# long.net
KiCad netlist of a schematic drawn in EAGLE
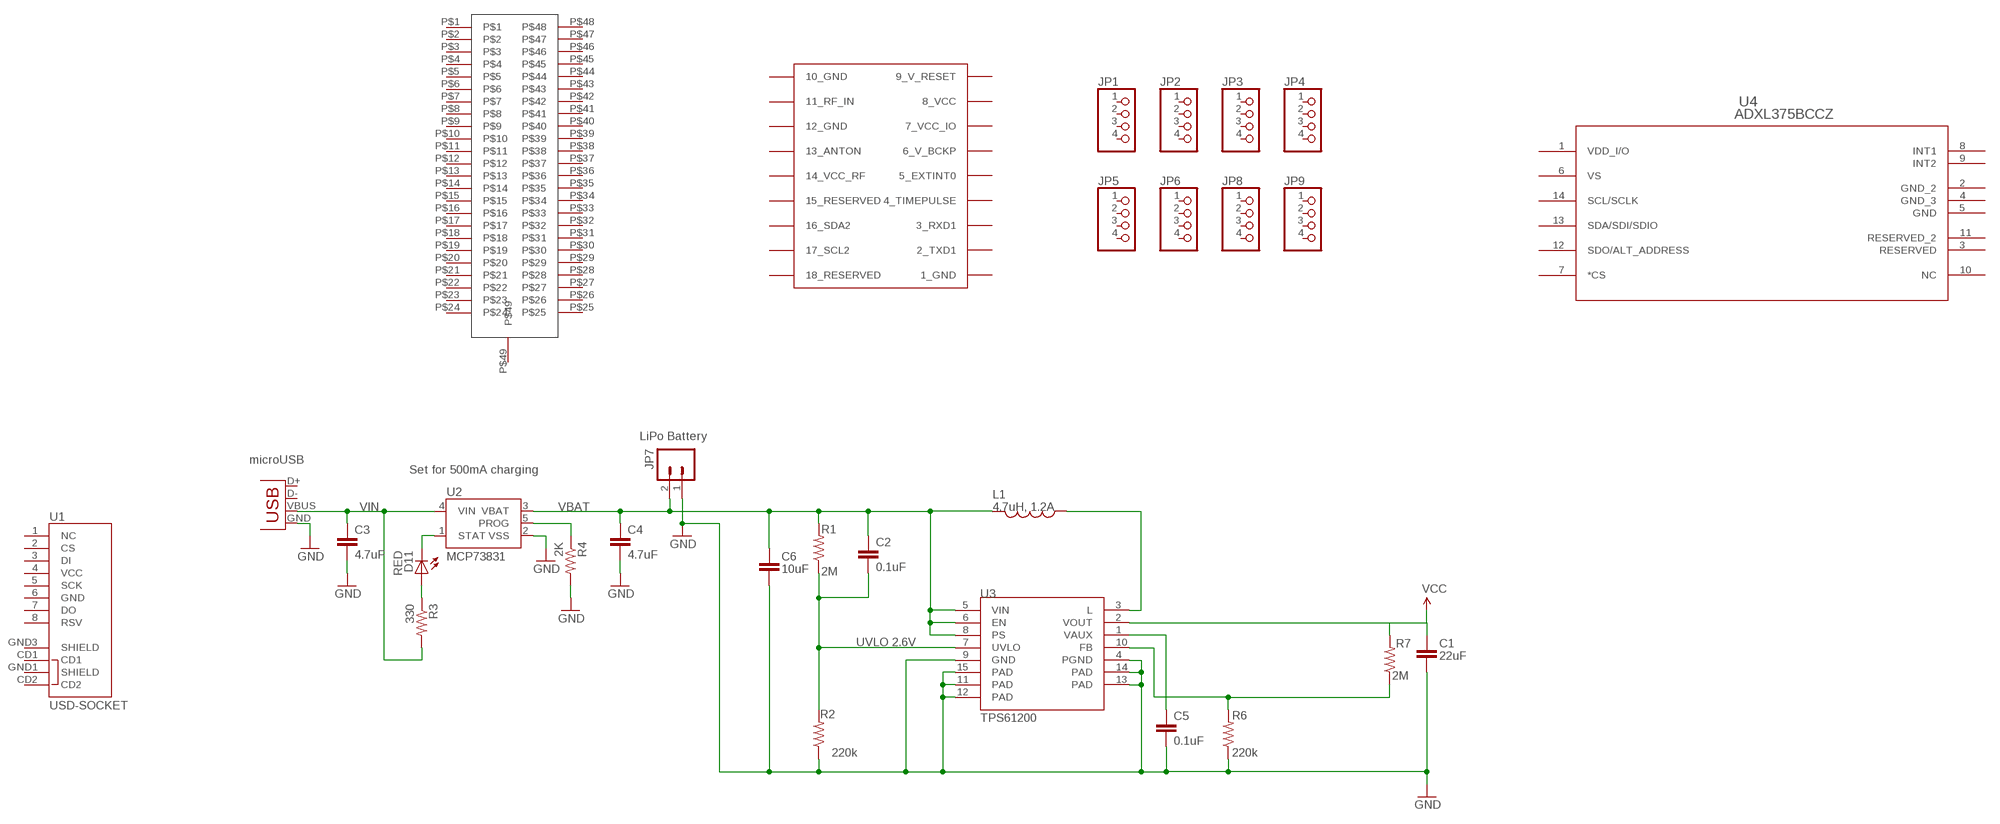
[diagram p0: schematic, sheet 1]

(export (version "E")
  (design (tool "Eeschema 10.0.6"))
  (components
    (comp (ref "C1")
      (value "22uF")
      (footprint "eagle-import:0805")
      (libsource (lib "eagle-import") (part "CAP0805"))
    )
    (comp (ref "C2")
      (value "0.1uF")
      (footprint "eagle-import:0603-CAP")
      (libsource (lib "eagle-import") (part "CAP0603-CAP"))
    )
    (comp (ref "C3")
      (value "4.7uF")
      (footprint "eagle-import:0402-CAP")
      (libsource (lib "eagle-import") (part "CAP0402-CAP"))
    )
    (comp (ref "C4")
      (value "4.7uF")
      (footprint "eagle-import:0402-CAP")
      (libsource (lib "eagle-import") (part "CAP0402-CAP"))
    )
    (comp (ref "C5")
      (value "0.1uF")
      (footprint "eagle-import:0603-CAP")
      (libsource (lib "eagle-import") (part "CAP0603-CAP"))
    )
    (comp (ref "C6")
      (value "10uF")
      (footprint "eagle-import:1206")
      (libsource (lib "eagle-import") (part "CAP1206"))
    )
    (comp (ref "D11")
      (value "RED")
      (footprint "eagle-import:LED-0603")
      (libsource (lib "eagle-import") (part "LED0603"))
    )
    (comp (ref "JP1")
      (value "PINHD-1X4")
      (footprint "eagle-import:1X04")
      (libsource (lib "eagle-import") (part "PINHD-1X4"))
    )
    (comp (ref "JP2")
      (value "PINHD-1X4")
      (footprint "eagle-import:1X04")
      (libsource (lib "eagle-import") (part "PINHD-1X4"))
    )
    (comp (ref "JP3")
      (value "PINHD-1X4")
      (footprint "eagle-import:1X04")
      (libsource (lib "eagle-import") (part "PINHD-1X4"))
    )
    (comp (ref "JP4")
      (value "PINHD-1X4")
      (footprint "eagle-import:1X04")
      (libsource (lib "eagle-import") (part "PINHD-1X4"))
    )
    (comp (ref "JP5")
      (value "PINHD-1X4")
      (footprint "eagle-import:1X04")
      (libsource (lib "eagle-import") (part "PINHD-1X4"))
    )
    (comp (ref "JP6")
      (value "PINHD-1X4")
      (footprint "eagle-import:1X04")
      (libsource (lib "eagle-import") (part "PINHD-1X4"))
    )
    (comp (ref "JP7")
      (value "LiPo Battery")
      (footprint "eagle-import:JST-2-SMD")
      (libsource (lib "eagle-import") (part "M02-JST-2MM-SMT"))
    )
    (comp (ref "JP8")
      (value "PINHD-1X4")
      (footprint "eagle-import:1X04")
      (libsource (lib "eagle-import") (part "PINHD-1X4"))
    )
    (comp (ref "JP9")
      (value "PINHD-1X4")
      (footprint "eagle-import:1X04")
      (libsource (lib "eagle-import") (part "PINHD-1X4"))
    )
    (comp (ref "L1")
      (value "4.7uH, 1.2A")
      (footprint "eagle-import:CDRH2D09")
      (libsource (lib "eagle-import") (part "INDUCTOR."))
    )
    (comp (ref "R1")
      (value "2M")
      (footprint "eagle-import:0603-RES")
      (libsource (lib "eagle-import") (part "RESISTOR0603-RES"))
    )
    (comp (ref "R2")
      (value "220k")
      (footprint "eagle-import:0603-RES")
      (libsource (lib "eagle-import") (part "RESISTOR0603-RES"))
    )
    (comp (ref "R3")
      (value "330")
      (footprint "eagle-import:0402-RES")
      (libsource (lib "eagle-import") (part "RESISTOR0402-RES"))
    )
    (comp (ref "R4")
      (value "2K")
      (footprint "eagle-import:0402-RES")
      (libsource (lib "eagle-import") (part "RESISTOR0402-RES"))
    )
    (comp (ref "R6")
      (value "220k")
      (footprint "eagle-import:0603-RES")
      (libsource (lib "eagle-import") (part "RESISTOR0603-RES"))
    )
    (comp (ref "R7")
      (value "2M")
      (footprint "eagle-import:0603-RES")
      (libsource (lib "eagle-import") (part "RESISTOR0603-RES"))
    )
    (comp (ref "U$1")
      (value "STM32F411CEU6")
      (footprint "eagle-import:STM32F411CEU6")
      (libsource (lib "eagle-import") (part "STM32F411CEU6"))
    )
    (comp (ref "U$2")
      (value "UBLOX_MAX")
      (footprint "eagle-import:UBLOX_MAX")
      (libsource (lib "eagle-import") (part "UBLOX_MAX"))
    )
    (comp (ref "U1")
      (value "USD-SOCKET")
      (footprint "eagle-import:MICROSD_1_1")
      (libsource (lib "eagle-import") (part "USD-SOCKET"))
    )
    (comp (ref "U2")
      (value "MCP73831")
      (footprint "eagle-import:SOT23-5")
      (libsource (lib "eagle-import") (part "MCP73831"))
    )
    (comp (ref "U3")
      (value "TPS61200")
      (footprint "eagle-import:QFN-10_PAD")
      (libsource (lib "eagle-import") (part "TPS61200"))
    )
    (comp (ref "U4")
      (value "ADXL375BCCZ")
      (footprint "eagle-import:LGA_CC-14-1")
      (libsource (lib "eagle-import") (part "ADXL375BCCZ"))
    )
    (comp (ref "X1")
      (value "Micro USB")
      (footprint "eagle-import:USB-MICROB")
      (libsource (lib "eagle-import") (part "USB-MICROB"))
    )
  )
  (nets
    (net (code "1") (name "/1_GND") (class "Default")
      (node (ref "U$2") (pin "1_GND") (pinfunction "1_GND_1_GND") (pintype "power_in"))
    )
    (net (code "2") (name "/7_VCC_IO") (class "Default")
      (node (ref "U$2") (pin "7_VCC_IO") (pinfunction "7_VCC_IO_7_VCC_IO") (pintype "power_in"))
    )
    (net (code "3") (name "/8_VCC") (class "Default")
      (node (ref "U$2") (pin "8_VCC") (pinfunction "8_VCC_8_VCC") (pintype "power_in"))
    )
    (net (code "4") (name "/9_V_RESET") (class "Default")
      (node (ref "U$2") (pin "9_V_RESET") (pinfunction "9_V_RESET_9_V_RESET") (pintype "power_in"))
    )
    (net (code "5") (name "/10_GND") (class "Default")
      (node (ref "U$2") (pin "10_GND") (pinfunction "10_GND_10_GND") (pintype "power_in"))
    )
    (net (code "6") (name "/12_GND") (class "Default")
      (node (ref "U$2") (pin "12_GND") (pinfunction "12_GND_12_GND") (pintype "power_in"))
    )
    (net (code "7") (name "/VBAT") (class "Default")
      (node (ref "C2") (pin "1") (pinfunction "1_1") (pintype "passive"))
      (node (ref "C4") (pin "1") (pinfunction "1_1") (pintype "passive"))
      (node (ref "C6") (pin "1") (pinfunction "1_1") (pintype "passive"))
      (node (ref "JP7") (pin "2") (pinfunction "2_2") (pintype "passive"))
      (node (ref "L1") (pin "P$2") (pinfunction "2_P$2") (pintype "passive"))
      (node (ref "R1") (pin "2") (pinfunction "2_2") (pintype "passive"))
      (node (ref "U2") (pin "3") (pinfunction "VBAT_3") (pintype "power_in"))
      (node (ref "U3") (pin "5") (pinfunction "VIN_5") (pintype "power_in"))
      (node (ref "U3") (pin "6") (pinfunction "EN_6") (pintype "input"))
      (node (ref "U3") (pin "8") (pinfunction "PS_8") (pintype "input"))
    )
    (net (code "8") (name "/VIN") (class "Default")
      (node (ref "C3") (pin "1") (pinfunction "1_1") (pintype "passive"))
      (node (ref "R3") (pin "2") (pinfunction "2_2") (pintype "passive"))
      (node (ref "U2") (pin "4") (pinfunction "VIN_4") (pintype "power_in"))
      (node (ref "X1") (pin "VBUS") (pinfunction "VBUS_VBUS") (pintype "bidirectional"))
    )
    (net (code "9") (name "GND") (class "Default")
      (node (ref "C1") (pin "2") (pinfunction "2_2") (pintype "passive"))
      (node (ref "C3") (pin "2") (pinfunction "2_2") (pintype "passive"))
      (node (ref "C4") (pin "2") (pinfunction "2_2") (pintype "passive"))
      (node (ref "C5") (pin "2") (pinfunction "2_2") (pintype "passive"))
      (node (ref "C6") (pin "2") (pinfunction "2_2") (pintype "passive"))
      (node (ref "JP7") (pin "1") (pinfunction "1_1") (pintype "passive"))
      (node (ref "R2") (pin "1") (pinfunction "1_1") (pintype "passive"))
      (node (ref "R4") (pin "2") (pinfunction "2_2") (pintype "passive"))
      (node (ref "R6") (pin "1") (pinfunction "1_1") (pintype "passive"))
      (node (ref "U2") (pin "2") (pinfunction "VSS_2") (pintype "power_in"))
      (node (ref "U3") (pin "11") (pinfunction "PAD_11") (pintype "power_in"))
      (node (ref "U3") (pin "12") (pinfunction "PAD_12") (pintype "power_in"))
      (node (ref "U3") (pin "13") (pinfunction "PAD_13") (pintype "power_in"))
      (node (ref "U3") (pin "14") (pinfunction "PAD_14") (pintype "power_in"))
      (node (ref "U3") (pin "15") (pinfunction "PAD_15") (pintype "power_in"))
      (node (ref "U3") (pin "4") (pinfunction "PGND_4") (pintype "power_in"))
      (node (ref "U3") (pin "9") (pinfunction "GND_9") (pintype "power_in"))
      (node (ref "X1") (pin "GND") (pinfunction "GND_GND") (pintype "bidirectional"))
    )
    (net (code "10") (name "Net-(D11-PadA)") (class "Default")
      (node (ref "D11") (pin "A") (pinfunction "A_A") (pintype "passive"))
      (node (ref "R3") (pin "1") (pinfunction "1_1") (pintype "passive"))
    )
    (net (code "11") (name "Net-(L1-1)") (class "Default")
      (node (ref "L1") (pin "P$1") (pinfunction "1_P$1") (pintype "passive"))
      (node (ref "U3") (pin "3") (pinfunction "L_3") (pintype "passive"))
    )
    (net (code "12") (name "Net-(U2-PROG)") (class "Default")
      (node (ref "R4") (pin "1") (pinfunction "1_1") (pintype "passive"))
      (node (ref "U2") (pin "5") (pinfunction "PROG_5") (pintype "input"))
    )
    (net (code "13") (name "Net-(U2-STAT)") (class "Default")
      (node (ref "D11") (pin "C") (pinfunction "C_C") (pintype "passive"))
      (node (ref "U2") (pin "1") (pinfunction "STAT_1") (pintype "output"))
    )
    (net (code "14") (name "Net-(U3-FB)") (class "Default")
      (node (ref "R6") (pin "2") (pinfunction "2_2") (pintype "passive"))
      (node (ref "R7") (pin "1") (pinfunction "1_1") (pintype "passive"))
      (node (ref "U3") (pin "10") (pinfunction "FB_10") (pintype "passive"))
    )
    (net (code "15") (name "Net-(U3-UVLO)") (class "Default")
      (node (ref "C2") (pin "2") (pinfunction "2_2") (pintype "passive"))
      (node (ref "R1") (pin "1") (pinfunction "1_1") (pintype "passive"))
      (node (ref "R2") (pin "2") (pinfunction "2_2") (pintype "passive"))
      (node (ref "U3") (pin "7") (pinfunction "UVLO_7") (pintype "passive"))
    )
    (net (code "16") (name "Net-(U3-VAUX)") (class "Default")
      (node (ref "C5") (pin "1") (pinfunction "1_1") (pintype "passive"))
      (node (ref "U3") (pin "1") (pinfunction "VAUX_1") (pintype "passive"))
    )
    (net (code "17") (name "VCC") (class "Default")
      (node (ref "C1") (pin "1") (pinfunction "1_1") (pintype "passive"))
      (node (ref "R7") (pin "2") (pinfunction "2_2") (pintype "passive"))
      (node (ref "U3") (pin "2") (pinfunction "VOUT_2") (pintype "passive"))
    )
    (net (code "18") (name "unconnected-(JP1-Pad1)") (class "Default")
      (node (ref "JP1") (pin "1") (pinfunction "1_1") (pintype "passive"))
    )
    (net (code "19") (name "unconnected-(JP1-Pad2)") (class "Default")
      (node (ref "JP1") (pin "2") (pinfunction "2_2") (pintype "passive"))
    )
    (net (code "20") (name "unconnected-(JP1-Pad3)") (class "Default")
      (node (ref "JP1") (pin "3") (pinfunction "3_3") (pintype "passive"))
    )
    (net (code "21") (name "unconnected-(JP1-Pad4)") (class "Default")
      (node (ref "JP1") (pin "4") (pinfunction "4_4") (pintype "passive"))
    )
    (net (code "22") (name "unconnected-(JP2-Pad1)") (class "Default")
      (node (ref "JP2") (pin "1") (pinfunction "1_1") (pintype "passive"))
    )
    (net (code "23") (name "unconnected-(JP2-Pad2)") (class "Default")
      (node (ref "JP2") (pin "2") (pinfunction "2_2") (pintype "passive"))
    )
    (net (code "24") (name "unconnected-(JP2-Pad3)") (class "Default")
      (node (ref "JP2") (pin "3") (pinfunction "3_3") (pintype "passive"))
    )
    (net (code "25") (name "unconnected-(JP2-Pad4)") (class "Default")
      (node (ref "JP2") (pin "4") (pinfunction "4_4") (pintype "passive"))
    )
    (net (code "26") (name "unconnected-(JP3-Pad1)") (class "Default")
      (node (ref "JP3") (pin "1") (pinfunction "1_1") (pintype "passive"))
    )
    (net (code "27") (name "unconnected-(JP3-Pad2)") (class "Default")
      (node (ref "JP3") (pin "2") (pinfunction "2_2") (pintype "passive"))
    )
    (net (code "28") (name "unconnected-(JP3-Pad3)") (class "Default")
      (node (ref "JP3") (pin "3") (pinfunction "3_3") (pintype "passive"))
    )
    (net (code "29") (name "unconnected-(JP3-Pad4)") (class "Default")
      (node (ref "JP3") (pin "4") (pinfunction "4_4") (pintype "passive"))
    )
    (net (code "30") (name "unconnected-(JP4-Pad1)") (class "Default")
      (node (ref "JP4") (pin "1") (pinfunction "1_1") (pintype "passive"))
    )
    (net (code "31") (name "unconnected-(JP4-Pad2)") (class "Default")
      (node (ref "JP4") (pin "2") (pinfunction "2_2") (pintype "passive"))
    )
    (net (code "32") (name "unconnected-(JP4-Pad3)") (class "Default")
      (node (ref "JP4") (pin "3") (pinfunction "3_3") (pintype "passive"))
    )
    (net (code "33") (name "unconnected-(JP4-Pad4)") (class "Default")
      (node (ref "JP4") (pin "4") (pinfunction "4_4") (pintype "passive"))
    )
    (net (code "34") (name "unconnected-(JP5-Pad1)") (class "Default")
      (node (ref "JP5") (pin "1") (pinfunction "1_1") (pintype "passive"))
    )
    (net (code "35") (name "unconnected-(JP5-Pad2)") (class "Default")
      (node (ref "JP5") (pin "2") (pinfunction "2_2") (pintype "passive"))
    )
    (net (code "36") (name "unconnected-(JP5-Pad3)") (class "Default")
      (node (ref "JP5") (pin "3") (pinfunction "3_3") (pintype "passive"))
    )
    (net (code "37") (name "unconnected-(JP5-Pad4)") (class "Default")
      (node (ref "JP5") (pin "4") (pinfunction "4_4") (pintype "passive"))
    )
    (net (code "38") (name "unconnected-(JP6-Pad1)") (class "Default")
      (node (ref "JP6") (pin "1") (pinfunction "1_1") (pintype "passive"))
    )
    (net (code "39") (name "unconnected-(JP6-Pad2)") (class "Default")
      (node (ref "JP6") (pin "2") (pinfunction "2_2") (pintype "passive"))
    )
    (net (code "40") (name "unconnected-(JP6-Pad3)") (class "Default")
      (node (ref "JP6") (pin "3") (pinfunction "3_3") (pintype "passive"))
    )
    (net (code "41") (name "unconnected-(JP6-Pad4)") (class "Default")
      (node (ref "JP6") (pin "4") (pinfunction "4_4") (pintype "passive"))
    )
    (net (code "42") (name "unconnected-(JP8-Pad1)") (class "Default")
      (node (ref "JP8") (pin "1") (pinfunction "1_1") (pintype "passive"))
    )
    (net (code "43") (name "unconnected-(JP8-Pad2)") (class "Default")
      (node (ref "JP8") (pin "2") (pinfunction "2_2") (pintype "passive"))
    )
    (net (code "44") (name "unconnected-(JP8-Pad3)") (class "Default")
      (node (ref "JP8") (pin "3") (pinfunction "3_3") (pintype "passive"))
    )
    (net (code "45") (name "unconnected-(JP8-Pad4)") (class "Default")
      (node (ref "JP8") (pin "4") (pinfunction "4_4") (pintype "passive"))
    )
    (net (code "46") (name "unconnected-(JP9-Pad1)") (class "Default")
      (node (ref "JP9") (pin "1") (pinfunction "1_1") (pintype "passive"))
    )
    (net (code "47") (name "unconnected-(JP9-Pad2)") (class "Default")
      (node (ref "JP9") (pin "2") (pinfunction "2_2") (pintype "passive"))
    )
    (net (code "48") (name "unconnected-(JP9-Pad3)") (class "Default")
      (node (ref "JP9") (pin "3") (pinfunction "3_3") (pintype "passive"))
    )
    (net (code "49") (name "unconnected-(JP9-Pad4)") (class "Default")
      (node (ref "JP9") (pin "4") (pinfunction "4_4") (pintype "passive"))
    )
    (net (code "50") (name "unconnected-(U$1-PadP$1)") (class "Default")
      (node (ref "U$1") (pin "P$1") (pinfunction "P$1_P$1") (pintype "bidirectional"))
    )
    (net (code "51") (name "unconnected-(U$1-PadP$2)") (class "Default")
      (node (ref "U$1") (pin "P$2") (pinfunction "P$2_P$2") (pintype "bidirectional"))
    )
    (net (code "52") (name "unconnected-(U$1-PadP$3)") (class "Default")
      (node (ref "U$1") (pin "P$3") (pinfunction "P$3_P$3") (pintype "bidirectional"))
    )
    (net (code "53") (name "unconnected-(U$1-PadP$4)") (class "Default")
      (node (ref "U$1") (pin "P$4") (pinfunction "P$4_P$4") (pintype "bidirectional"))
    )
    (net (code "54") (name "unconnected-(U$1-PadP$5)") (class "Default")
      (node (ref "U$1") (pin "P$5") (pinfunction "P$5_P$5") (pintype "bidirectional"))
    )
    (net (code "55") (name "unconnected-(U$1-PadP$6)") (class "Default")
      (node (ref "U$1") (pin "P$6") (pinfunction "P$6_P$6") (pintype "bidirectional"))
    )
    (net (code "56") (name "unconnected-(U$1-PadP$7)") (class "Default")
      (node (ref "U$1") (pin "P$7") (pinfunction "P$7_P$7") (pintype "bidirectional"))
    )
    (net (code "57") (name "unconnected-(U$1-PadP$8)") (class "Default")
      (node (ref "U$1") (pin "P$8") (pinfunction "P$8_P$8") (pintype "bidirectional"))
    )
    (net (code "58") (name "unconnected-(U$1-PadP$9)") (class "Default")
      (node (ref "U$1") (pin "P$9") (pinfunction "P$9_P$9") (pintype "bidirectional"))
    )
    (net (code "59") (name "unconnected-(U$1-PadP$10)") (class "Default")
      (node (ref "U$1") (pin "P$10") (pinfunction "P$10_P$10") (pintype "bidirectional"))
    )
    (net (code "60") (name "unconnected-(U$1-PadP$11)") (class "Default")
      (node (ref "U$1") (pin "P$11") (pinfunction "P$11_P$11") (pintype "bidirectional"))
    )
    (net (code "61") (name "unconnected-(U$1-PadP$12)") (class "Default")
      (node (ref "U$1") (pin "P$12") (pinfunction "P$12_P$12") (pintype "bidirectional"))
    )
    (net (code "62") (name "unconnected-(U$1-PadP$13)") (class "Default")
      (node (ref "U$1") (pin "P$13") (pinfunction "P$13_P$13") (pintype "bidirectional"))
    )
    (net (code "63") (name "unconnected-(U$1-PadP$14)") (class "Default")
      (node (ref "U$1") (pin "P$14") (pinfunction "P$14_P$14") (pintype "bidirectional"))
    )
    (net (code "64") (name "unconnected-(U$1-PadP$15)") (class "Default")
      (node (ref "U$1") (pin "P$15") (pinfunction "P$15_P$15") (pintype "bidirectional"))
    )
    (net (code "65") (name "unconnected-(U$1-PadP$16)") (class "Default")
      (node (ref "U$1") (pin "P$16") (pinfunction "P$16_P$16") (pintype "bidirectional"))
    )
    (net (code "66") (name "unconnected-(U$1-PadP$17)") (class "Default")
      (node (ref "U$1") (pin "P$17") (pinfunction "P$17_P$17") (pintype "bidirectional"))
    )
    (net (code "67") (name "unconnected-(U$1-PadP$18)") (class "Default")
      (node (ref "U$1") (pin "P$18") (pinfunction "P$18_P$18") (pintype "bidirectional"))
    )
    (net (code "68") (name "unconnected-(U$1-PadP$19)") (class "Default")
      (node (ref "U$1") (pin "P$19") (pinfunction "P$19_P$19") (pintype "bidirectional"))
    )
    (net (code "69") (name "unconnected-(U$1-PadP$20)") (class "Default")
      (node (ref "U$1") (pin "P$20") (pinfunction "P$20_P$20") (pintype "bidirectional"))
    )
    (net (code "70") (name "unconnected-(U$1-PadP$21)") (class "Default")
      (node (ref "U$1") (pin "P$21") (pinfunction "P$21_P$21") (pintype "bidirectional"))
    )
    (net (code "71") (name "unconnected-(U$1-PadP$22)") (class "Default")
      (node (ref "U$1") (pin "P$22") (pinfunction "P$22_P$22") (pintype "bidirectional"))
    )
    (net (code "72") (name "unconnected-(U$1-PadP$23)") (class "Default")
      (node (ref "U$1") (pin "P$23") (pinfunction "P$23_P$23") (pintype "bidirectional"))
    )
    (net (code "73") (name "unconnected-(U$1-PadP$24)") (class "Default")
      (node (ref "U$1") (pin "P$24") (pinfunction "P$24_P$24") (pintype "bidirectional"))
    )
    (net (code "74") (name "unconnected-(U$1-PadP$25)") (class "Default")
      (node (ref "U$1") (pin "P$25") (pinfunction "P$25_P$25") (pintype "bidirectional"))
    )
    (net (code "75") (name "unconnected-(U$1-PadP$26)") (class "Default")
      (node (ref "U$1") (pin "P$26") (pinfunction "P$26_P$26") (pintype "bidirectional"))
    )
    (net (code "76") (name "unconnected-(U$1-PadP$27)") (class "Default")
      (node (ref "U$1") (pin "P$27") (pinfunction "P$27_P$27") (pintype "bidirectional"))
    )
    (net (code "77") (name "unconnected-(U$1-PadP$28)") (class "Default")
      (node (ref "U$1") (pin "P$28") (pinfunction "P$28_P$28") (pintype "bidirectional"))
    )
    (net (code "78") (name "unconnected-(U$1-PadP$29)") (class "Default")
      (node (ref "U$1") (pin "P$29") (pinfunction "P$29_P$29") (pintype "bidirectional"))
    )
    (net (code "79") (name "unconnected-(U$1-PadP$30)") (class "Default")
      (node (ref "U$1") (pin "P$30") (pinfunction "P$30_P$30") (pintype "bidirectional"))
    )
    (net (code "80") (name "unconnected-(U$1-PadP$31)") (class "Default")
      (node (ref "U$1") (pin "P$31") (pinfunction "P$31_P$31") (pintype "bidirectional"))
    )
    (net (code "81") (name "unconnected-(U$1-PadP$32)") (class "Default")
      (node (ref "U$1") (pin "P$32") (pinfunction "P$32_P$32") (pintype "bidirectional"))
    )
    (net (code "82") (name "unconnected-(U$1-PadP$33)") (class "Default")
      (node (ref "U$1") (pin "P$33") (pinfunction "P$33_P$33") (pintype "bidirectional"))
    )
    (net (code "83") (name "unconnected-(U$1-PadP$34)") (class "Default")
      (node (ref "U$1") (pin "P$34") (pinfunction "P$34_P$34") (pintype "bidirectional"))
    )
    (net (code "84") (name "unconnected-(U$1-PadP$35)") (class "Default")
      (node (ref "U$1") (pin "P$35") (pinfunction "P$35_P$35") (pintype "bidirectional"))
    )
    (net (code "85") (name "unconnected-(U$1-PadP$36)") (class "Default")
      (node (ref "U$1") (pin "P$36") (pinfunction "P$36_P$36") (pintype "bidirectional"))
    )
    (net (code "86") (name "unconnected-(U$1-PadP$37)") (class "Default")
      (node (ref "U$1") (pin "P$37") (pinfunction "P$37_P$37") (pintype "bidirectional"))
    )
    (net (code "87") (name "unconnected-(U$1-PadP$38)") (class "Default")
      (node (ref "U$1") (pin "P$38") (pinfunction "P$38_P$38") (pintype "bidirectional"))
    )
    (net (code "88") (name "unconnected-(U$1-PadP$39)") (class "Default")
      (node (ref "U$1") (pin "P$39") (pinfunction "P$39_P$39") (pintype "bidirectional"))
    )
    (net (code "89") (name "unconnected-(U$1-PadP$40)") (class "Default")
      (node (ref "U$1") (pin "P$40") (pinfunction "P$40_P$40") (pintype "bidirectional"))
    )
    (net (code "90") (name "unconnected-(U$1-PadP$41)") (class "Default")
      (node (ref "U$1") (pin "P$41") (pinfunction "P$41_P$41") (pintype "bidirectional"))
    )
    (net (code "91") (name "unconnected-(U$1-PadP$42)") (class "Default")
      (node (ref "U$1") (pin "P$42") (pinfunction "P$42_P$42") (pintype "bidirectional"))
    )
    (net (code "92") (name "unconnected-(U$1-PadP$43)") (class "Default")
      (node (ref "U$1") (pin "P$43") (pinfunction "P$43_P$43") (pintype "bidirectional"))
    )
    (net (code "93") (name "unconnected-(U$1-PadP$44)") (class "Default")
      (node (ref "U$1") (pin "P$44") (pinfunction "P$44_P$44") (pintype "bidirectional"))
    )
    (net (code "94") (name "unconnected-(U$1-PadP$45)") (class "Default")
      (node (ref "U$1") (pin "P$45") (pinfunction "P$45_P$45") (pintype "bidirectional"))
    )
    (net (code "95") (name "unconnected-(U$1-PadP$46)") (class "Default")
      (node (ref "U$1") (pin "P$46") (pinfunction "P$46_P$46") (pintype "bidirectional"))
    )
    (net (code "96") (name "unconnected-(U$1-PadP$47)") (class "Default")
      (node (ref "U$1") (pin "P$47") (pinfunction "P$47_P$47") (pintype "bidirectional"))
    )
    (net (code "97") (name "unconnected-(U$1-PadP$48)") (class "Default")
      (node (ref "U$1") (pin "P$48") (pinfunction "P$48_P$48") (pintype "bidirectional"))
    )
    (net (code "98") (name "unconnected-(U$1-PadP$49)") (class "Default")
      (node (ref "U$1") (pin "P$49") (pinfunction "P$49_P$49") (pintype "bidirectional"))
    )
    (net (code "99") (name "unconnected-(U$2-Pad2_TXD1)") (class "Default")
      (node (ref "U$2") (pin "2_TXD1") (pinfunction "2_TXD1_2_TXD1") (pintype "bidirectional"))
    )
    (net (code "100") (name "unconnected-(U$2-Pad3_RXD1)") (class "Default")
      (node (ref "U$2") (pin "3_RXD1") (pinfunction "3_RXD1_3_RXD1") (pintype "bidirectional"))
    )
    (net (code "101") (name "unconnected-(U$2-Pad4_TIMEPULSE)") (class "Default")
      (node (ref "U$2") (pin "4_TIMEPULSE") (pinfunction "4_TIMEPULSE_4_TIMEPULSE") (pintype "bidirectional"))
    )
    (net (code "102") (name "unconnected-(U$2-Pad5_EXTINT0)") (class "Default")
      (node (ref "U$2") (pin "5_EXTINT0") (pinfunction "5_EXTINT0_5_EXTINT0") (pintype "bidirectional"))
    )
    (net (code "103") (name "unconnected-(U$2-Pad6_V_BCKP)") (class "Default")
      (node (ref "U$2") (pin "6_V_BCKP") (pinfunction "6_V_BCKP_6_V_BCKP") (pintype "bidirectional"))
    )
    (net (code "104") (name "unconnected-(U$2-Pad11_RF_IN)") (class "Default")
      (node (ref "U$2") (pin "11_RF_IN") (pinfunction "11_RF_IN_11_RF_IN") (pintype "bidirectional"))
    )
    (net (code "105") (name "unconnected-(U$2-Pad13_ANTON)") (class "Default")
      (node (ref "U$2") (pin "13_ANTON") (pinfunction "13_ANTON_13_ANTON") (pintype "bidirectional"))
    )
    (net (code "106") (name "unconnected-(U$2-Pad14_VCC_RF)") (class "Default")
      (node (ref "U$2") (pin "14_VCC_RF") (pinfunction "14_VCC_RF_14_VCC_RF") (pintype "bidirectional"))
    )
    (net (code "107") (name "unconnected-(U$2-Pad15_RESERVED)") (class "Default")
      (node (ref "U$2") (pin "15_RESERVED") (pinfunction "15_RESERVED_15_RESERVED") (pintype "bidirectional"))
    )
    (net (code "108") (name "unconnected-(U$2-Pad16_SDA2)") (class "Default")
      (node (ref "U$2") (pin "16_SDA2") (pinfunction "16_SDA2_16_SDA2") (pintype "bidirectional"))
    )
    (net (code "109") (name "unconnected-(U$2-Pad17_SCL2)") (class "Default")
      (node (ref "U$2") (pin "17_SCL2") (pinfunction "17_SCL2_17_SCL2") (pintype "bidirectional"))
    )
    (net (code "110") (name "unconnected-(U$2-Pad18_RESERVED)") (class "Default")
      (node (ref "U$2") (pin "18_RESERVED") (pinfunction "18_RESERVED_18_RESERVED") (pintype "bidirectional"))
    )
    (net (code "111") (name "unconnected-(U1-CS-Pad2)") (class "Default")
      (node (ref "U1") (pin "2") (pinfunction "CS_2") (pintype "bidirectional"))
    )
    (net (code "112") (name "unconnected-(U1-DI-Pad3)") (class "Default")
      (node (ref "U1") (pin "3") (pinfunction "DI_3") (pintype "bidirectional"))
    )
    (net (code "113") (name "unconnected-(U1-DO-Pad7)") (class "Default")
      (node (ref "U1") (pin "7") (pinfunction "DO_7") (pintype "bidirectional"))
    )
    (net (code "114") (name "unconnected-(U1-GND-Pad6)") (class "Default")
      (node (ref "U1") (pin "6") (pinfunction "GND_6") (pintype "bidirectional"))
    )
    (net (code "115") (name "unconnected-(U1-NC-Pad1)") (class "Default")
      (node (ref "U1") (pin "1") (pinfunction "NC_1") (pintype "bidirectional"))
    )
    (net (code "116") (name "unconnected-(U1-PadCD1)") (class "Default")
      (node (ref "U1") (pin "CD1") (pinfunction "CD1_CD1") (pintype "bidirectional"))
    )
    (net (code "117") (name "unconnected-(U1-PadCD2)") (class "Default")
      (node (ref "U1") (pin "CD2") (pinfunction "CD2_CD2") (pintype "bidirectional"))
    )
    (net (code "118") (name "unconnected-(U1-RSV-Pad8)") (class "Default")
      (node (ref "U1") (pin "8") (pinfunction "RSV_8") (pintype "bidirectional"))
    )
    (net (code "119") (name "unconnected-(U1-SCK-Pad5)") (class "Default")
      (node (ref "U1") (pin "5") (pinfunction "SCK_5") (pintype "bidirectional"))
    )
    (net (code "120") (name "unconnected-(U1-SHIELD-PadGND1)") (class "Default")
      (node (ref "U1") (pin "GND1") (pinfunction "SHIELD_GND1") (pintype "bidirectional"))
    )
    (net (code "121") (name "unconnected-(U1-SHIELD-PadGND3)") (class "Default")
      (node (ref "U1") (pin "GND3") (pinfunction "SHIELD_GND3") (pintype "bidirectional"))
    )
    (net (code "122") (name "unconnected-(U1-VCC-Pad4)") (class "Default")
      (node (ref "U1") (pin "4") (pinfunction "VCC_4") (pintype "bidirectional"))
    )
    (net (code "123") (name "unconnected-(U4-*CS-Pad7)") (class "Default")
      (node (ref "U4") (pin "7") (pinfunction "*CS_7") (pintype "passive"))
    )
    (net (code "124") (name "unconnected-(U4-GND-Pad5)") (class "Default")
      (node (ref "U4") (pin "5") (pinfunction "GND_5") (pintype "passive"))
    )
    (net (code "125") (name "unconnected-(U4-GND_2-Pad2)") (class "Default")
      (node (ref "U4") (pin "2") (pinfunction "GND_2_2") (pintype "passive"))
    )
    (net (code "126") (name "unconnected-(U4-GND_3-Pad4)") (class "Default")
      (node (ref "U4") (pin "4") (pinfunction "GND_3_4") (pintype "passive"))
    )
    (net (code "127") (name "unconnected-(U4-INT1-Pad8)") (class "Default")
      (node (ref "U4") (pin "8") (pinfunction "INT1_8") (pintype "passive"))
    )
    (net (code "128") (name "unconnected-(U4-INT2-Pad9)") (class "Default")
      (node (ref "U4") (pin "9") (pinfunction "INT2_9") (pintype "passive"))
    )
    (net (code "129") (name "unconnected-(U4-NC-Pad10)") (class "Default")
      (node (ref "U4") (pin "10") (pinfunction "NC_10") (pintype "passive"))
    )
    (net (code "130") (name "unconnected-(U4-RESERVED-Pad3)") (class "Default")
      (node (ref "U4") (pin "3") (pinfunction "RESERVED_3") (pintype "passive"))
    )
    (net (code "131") (name "unconnected-(U4-RESERVED_2-Pad11)") (class "Default")
      (node (ref "U4") (pin "11") (pinfunction "RESERVED_2_11") (pintype "passive"))
    )
    (net (code "132") (name "unconnected-(U4-SCL{slash}SCLK-Pad14)") (class "Default")
      (node (ref "U4") (pin "14") (pinfunction "SCL/SCLK_14") (pintype "passive"))
    )
    (net (code "133") (name "unconnected-(U4-SDA{slash}SDI{slash}SDIO-Pad13)") (class "Default")
      (node (ref "U4") (pin "13") (pinfunction "SDA/SDI/SDIO_13") (pintype "passive"))
    )
    (net (code "134") (name "unconnected-(U4-SDO{slash}ALT_ADDRESS-Pad12)") (class "Default")
      (node (ref "U4") (pin "12") (pinfunction "SDO/ALT_ADDRESS_12") (pintype "passive"))
    )
    (net (code "135") (name "unconnected-(U4-VDD_I{slash}O-Pad1)") (class "Default")
      (node (ref "U4") (pin "1") (pinfunction "VDD_I/O_1") (pintype "passive"))
    )
    (net (code "136") (name "unconnected-(U4-VS-Pad6)") (class "Default")
      (node (ref "U4") (pin "6") (pinfunction "VS_6") (pintype "passive"))
    )
    (net (code "137") (name "unconnected-(X1-PadD+)") (class "Default")
      (node (ref "X1") (pin "D+") (pinfunction "D+_D+") (pintype "bidirectional"))
    )
    (net (code "138") (name "unconnected-(X1-PadD-)") (class "Default")
      (node (ref "X1") (pin "D-") (pinfunction "D-_D-") (pintype "bidirectional"))
    )
  )
)
